# JLC.net
KiCad netlist of a schematic drawn in EasyEDA Pro
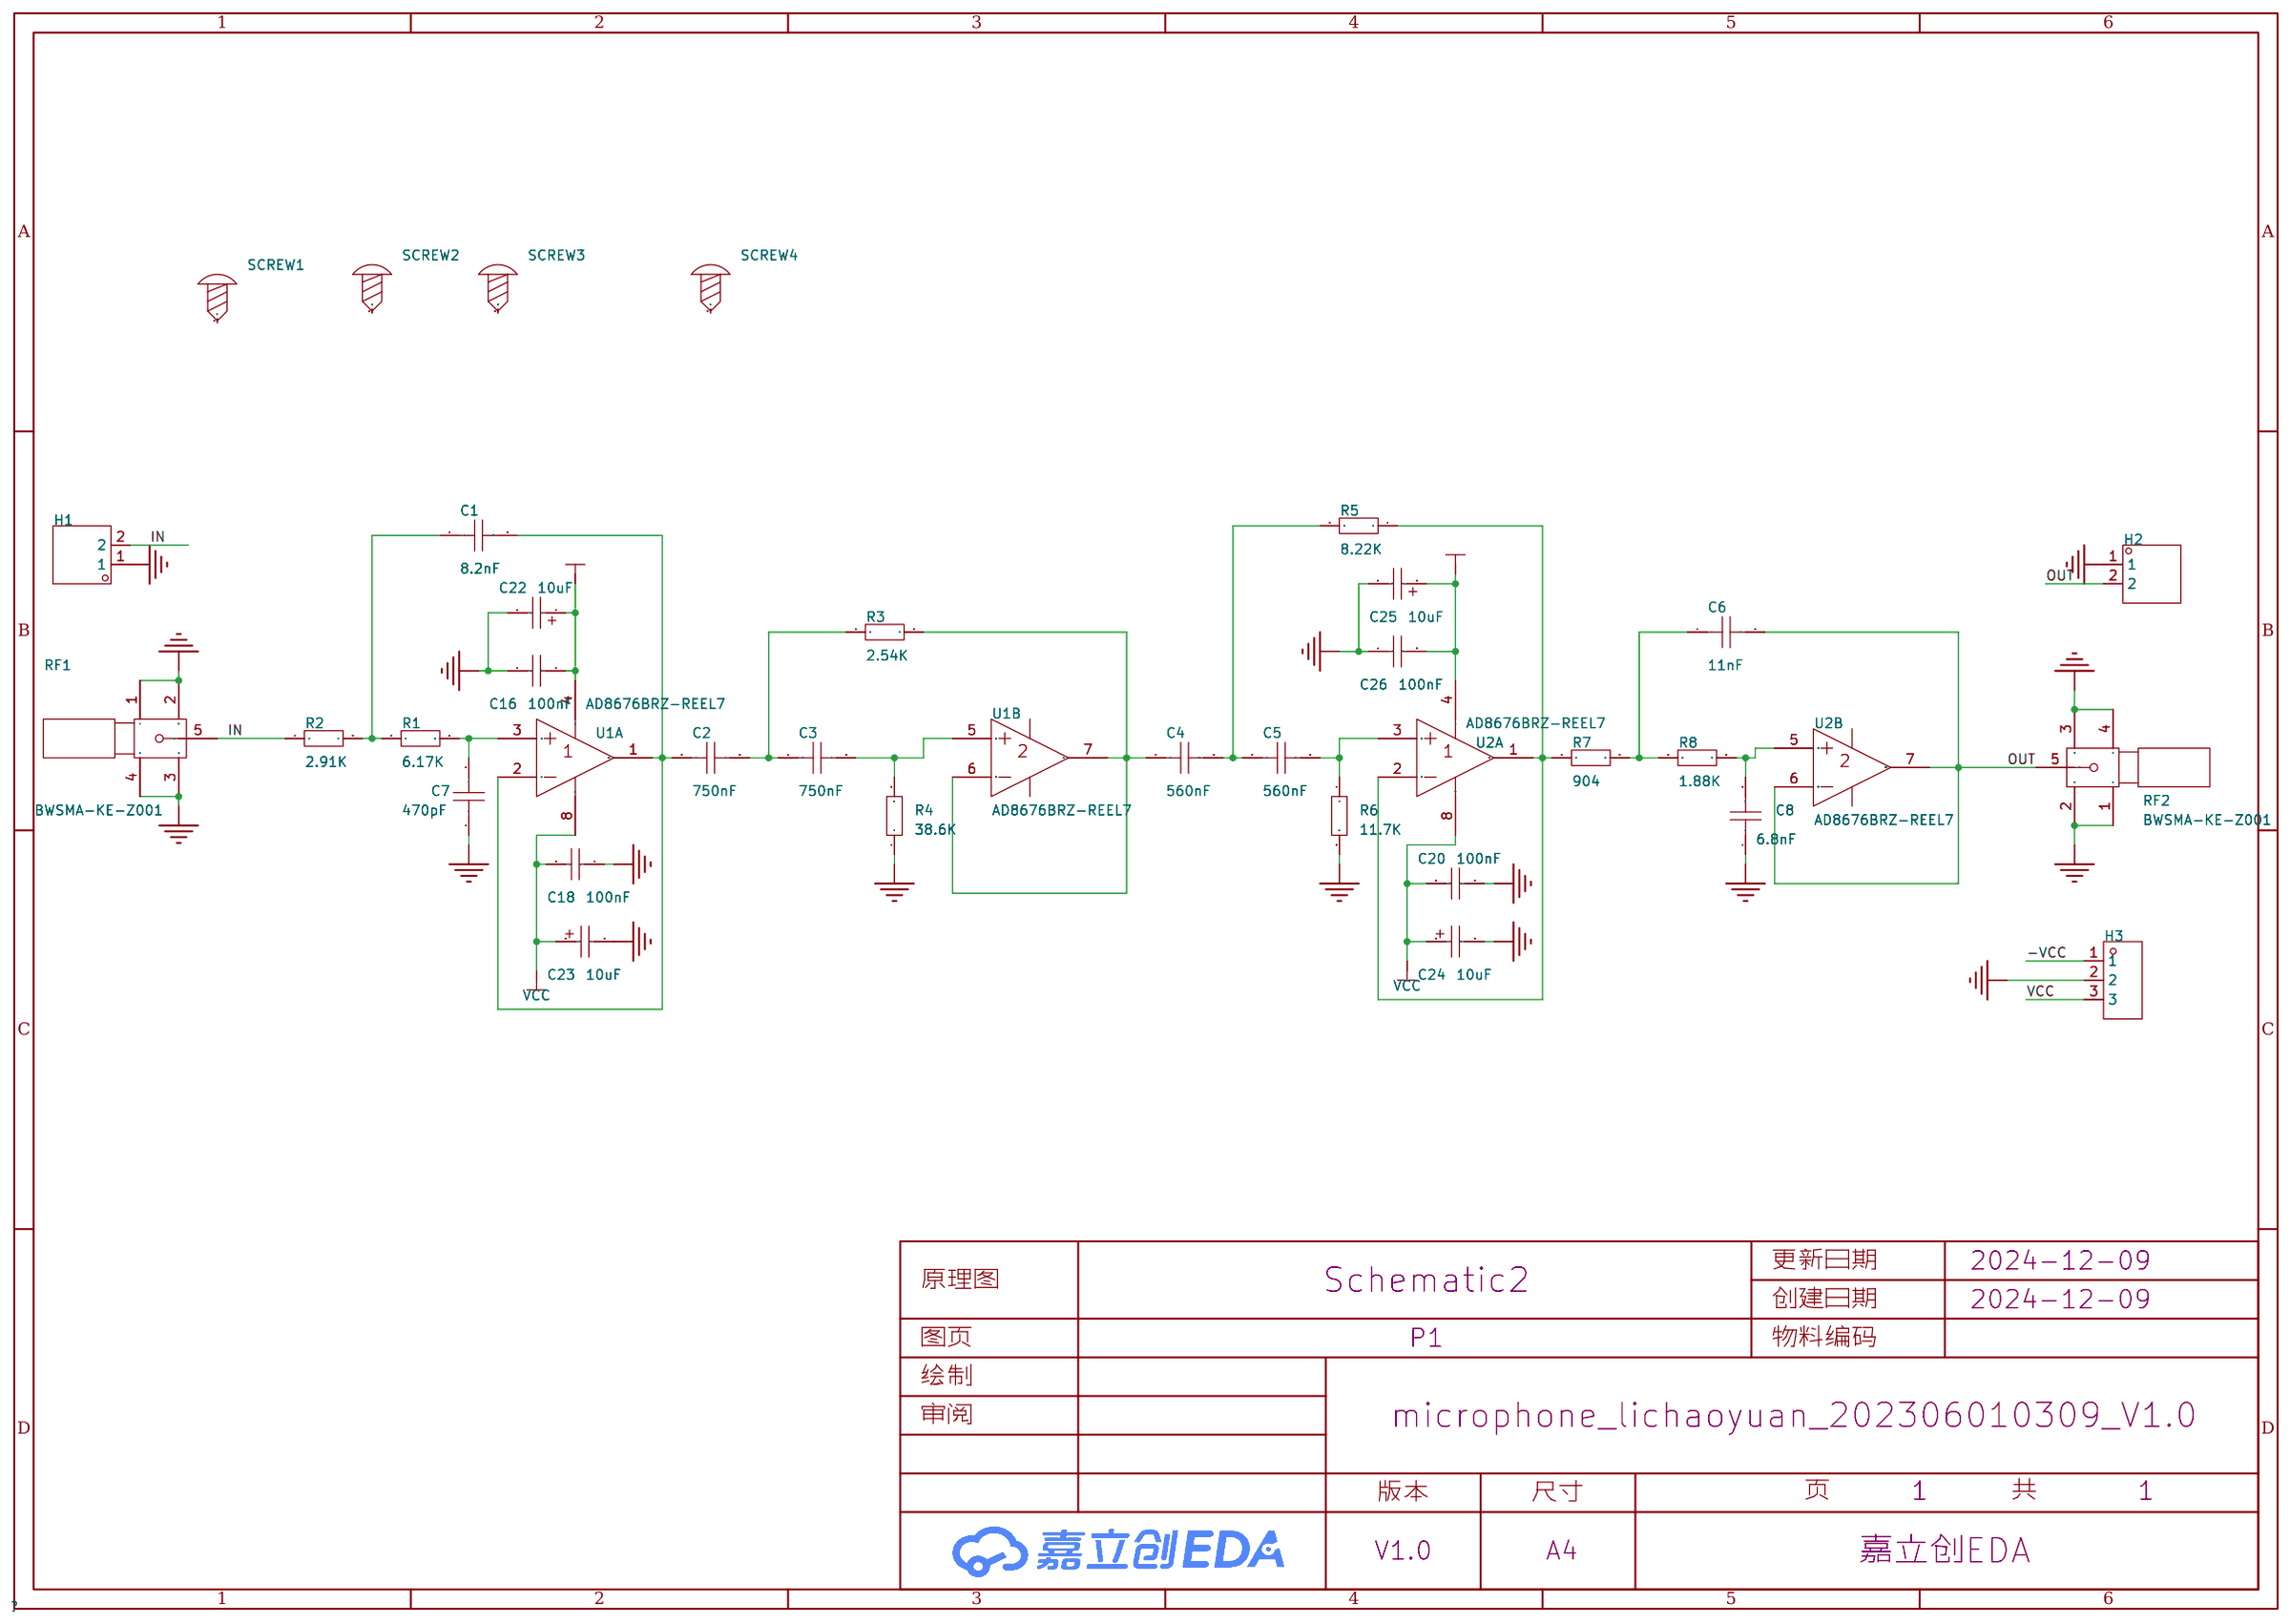
[diagram p0: schematic sheet]

(export (version "E")
  (design (tool "Eeschema 10.0.6"))
  (components
    (comp (ref "C1")
      (value "8.2nF")
      (footprint "easyedapro:C0603")
      (libsource (lib "easyedapro") (part "CapAcitance"))
    )
    (comp (ref "C2")
      (value "750nF")
      (footprint "easyedapro:C0603")
      (libsource (lib "easyedapro") (part "CapAcitance"))
    )
    (comp (ref "C3")
      (value "750nF")
      (footprint "easyedapro:C0603")
      (libsource (lib "easyedapro") (part "CapAcitance"))
    )
    (comp (ref "C4")
      (value "560nF")
      (footprint "easyedapro:C0603")
      (libsource (lib "easyedapro") (part "CapAcitance"))
    )
    (comp (ref "C5")
      (value "560nF")
      (footprint "easyedapro:C0603")
      (libsource (lib "easyedapro") (part "CapAcitance"))
    )
    (comp (ref "C6")
      (value "11nF")
      (footprint "easyedapro:C0603")
      (libsource (lib "easyedapro") (part "CapAcitance"))
    )
    (comp (ref "C7")
      (value "470pF")
      (footprint "easyedapro:C0603")
      (libsource (lib "easyedapro") (part "CapAcitance"))
    )
    (comp (ref "C8")
      (value "6.8nF")
      (footprint "easyedapro:C0603")
      (libsource (lib "easyedapro") (part "CapAcitance"))
    )
    (comp (ref "C16")
      (value "100nF")
      (footprint "easyedapro:C0805")
      (description "容值:100nF;精度:±5%;额定电压:50V;材质(温度系数):X7R;")
      (fields (field (name "Manufacturer Part") "0805B104J500NT") (field (name "Manufacturer") "FH(风华)"))
      (libsource (lib "easyedapro") (part "0805B104J500NT"))
    )
    (comp (ref "C18")
      (value "100nF")
      (footprint "easyedapro:C0805")
      (description "容值:100nF;精度:±5%;额定电压:50V;材质(温度系数):X7R;")
      (fields (field (name "Manufacturer Part") "0805B104J500NT") (field (name "Manufacturer") "FH(风华)"))
      (libsource (lib "easyedapro") (part "0805B104J500NT"))
    )
    (comp (ref "C20")
      (value "100nF")
      (footprint "easyedapro:C0805")
      (description "容值:100nF;精度:±5%;额定电压:50V;材质(温度系数):X7R;")
      (fields (field (name "Manufacturer Part") "0805B104J500NT") (field (name "Manufacturer") "FH(风华)"))
      (libsource (lib "easyedapro") (part "0805B104J500NT"))
    )
    (comp (ref "C22")
      (value "10uF")
      (footprint "easyedapro:C_Ele_SMD_5x5.4mm")
      (libsource (lib "easyedapro") (part "CAP"))
    )
    (comp (ref "C23")
      (value "10uF")
      (footprint "easyedapro:C_Ele_SMD_5x5.4mm")
      (libsource (lib "easyedapro") (part "CAP"))
    )
    (comp (ref "C24")
      (value "10uF")
      (footprint "easyedapro:C_Ele_SMD_5x5.4mm")
      (libsource (lib "easyedapro") (part "CAP"))
    )
    (comp (ref "C25")
      (value "10uF")
      (footprint "easyedapro:C_Ele_SMD_5x5.4mm")
      (libsource (lib "easyedapro") (part "CAP"))
    )
    (comp (ref "C26")
      (value "100nF")
      (footprint "easyedapro:C0805")
      (description "容值:100nF;精度:±5%;额定电压:50V;材质(温度系数):X7R;")
      (fields (field (name "Manufacturer Part") "0805B104J500NT") (field (name "Manufacturer") "FH(风华)"))
      (libsource (lib "easyedapro") (part "0805B104J500NT"))
    )
    (comp (ref "H1")
      (value "~")
      (footprint "easyedapro:HDR-TH_2P-P2.54-V-M-1")
      (libsource (lib "easyedapro") (part "210S-1*2P L=11.6MMGold-plated black"))
    )
    (comp (ref "H2")
      (value "~")
      (footprint "easyedapro:HDR-TH_2P-P2.54-V-M-1")
      (libsource (lib "easyedapro") (part "210S-1*2P L=11.6MMGold-plated black"))
    )
    (comp (ref "H3")
      (value "~")
      (footprint "easyedapro:HDR-TH_3P-P2.54-V-F")
      (libsource (lib "easyedapro") (part "PM254V-11-03-H85"))
    )
    (comp (ref "R1")
      (value "6.17K")
      (footprint "easyedapro:R0603")
      (libsource (lib "easyedapro") (part "电阻"))
    )
    (comp (ref "R2")
      (value "2.91K")
      (footprint "easyedapro:R0603")
      (libsource (lib "easyedapro") (part "电阻"))
    )
    (comp (ref "R3")
      (value "2.54K")
      (footprint "easyedapro:R0603")
      (libsource (lib "easyedapro") (part "电阻"))
    )
    (comp (ref "R4")
      (value "38.6K")
      (footprint "easyedapro:R0603")
      (libsource (lib "easyedapro") (part "电阻"))
    )
    (comp (ref "R5")
      (value "8.22K")
      (footprint "easyedapro:R0603")
      (libsource (lib "easyedapro") (part "电阻"))
    )
    (comp (ref "R6")
      (value "11.7K")
      (footprint "easyedapro:R0603")
      (libsource (lib "easyedapro") (part "电阻"))
    )
    (comp (ref "R7") (value "904") (footprint "easyedapro:R0603") (libsource (lib "easyedapro") (part "电阻")))
    (comp (ref "R8")
      (value "1.88K")
      (footprint "easyedapro:R0603")
      (libsource (lib "easyedapro") (part "电阻"))
    )
    (comp (ref "RF1")
      (value "BWSMA-KE-Z001")
      (footprint "easyedapro:SMA-TH_BWSMA-KE-Z001")
      (fields (field (name "Manufacturer") "BAT WIRELESS(蝙蝠无线)"))
      (libsource (lib "easyedapro") (part "BWSMA-KE-Z001"))
    )
    (comp (ref "RF2")
      (value "BWSMA-KE-Z001")
      (footprint "easyedapro:SMA-TH_BWSMA-KE-Z001")
      (fields (field (name "Manufacturer") "BAT WIRELESS(蝙蝠无线)"))
      (libsource (lib "easyedapro") (part "BWSMA-KE-Z001"))
    )
    (comp (ref "SCREW1")
      (value "~")
      (footprint "easyedapro:M2螺丝")
      (libsource (lib "easyedapro") (part "螺丝孔"))
    )
    (comp (ref "SCREW2")
      (value "~")
      (footprint "easyedapro:M2螺丝")
      (libsource (lib "easyedapro") (part "螺丝孔"))
    )
    (comp (ref "SCREW3")
      (value "~")
      (footprint "easyedapro:M2螺丝")
      (libsource (lib "easyedapro") (part "螺丝孔"))
    )
    (comp (ref "SCREW4")
      (value "~")
      (footprint "easyedapro:M2螺丝")
      (libsource (lib "easyedapro") (part "螺丝孔"))
    )
    (comp (ref "U1")
      (value "AD8676BRZ-REEL7")
      (footprint "easyedapro:SOIC-8_L4.9-W3.9-P1.27-LS6.0-BL")
      (description "超高精度、36 V、2.8 nV/√Hz双路RRO运算放大器")
      (fields (field (name "Manufacturer") "ADI(亚德诺)"))
      (libsource (lib "easyedapro") (part "AD8676BRZ-REEL7"))
    )
    (comp (ref "U2")
      (value "AD8676BRZ-REEL7")
      (footprint "easyedapro:SOIC-8_L4.9-W3.9-P1.27-LS6.0-BL")
      (description "超高精度、36 V、2.8 nV/√Hz双路RRO运算放大器")
      (fields (field (name "Manufacturer") "ADI(亚德诺)"))
      (libsource (lib "easyedapro") (part "AD8676BRZ-REEL7"))
    )
  )
  (nets
    (net (code "1") (name "-VCC") (class "Default")
      (node (ref "C16") (pin "2") (pinfunction "2_2") (pintype "input"))
      (node (ref "C22") (pin "1") (pinfunction "1_1") (pintype "input"))
      (node (ref "C25") (pin "1") (pinfunction "1_1") (pintype "input"))
      (node (ref "C26") (pin "2") (pinfunction "2_2") (pintype "input"))
      (node (ref "H3") (pin "1") (pinfunction "1_1") (pintype "unspecified"))
      (node (ref "U1") (pin "4") (pinfunction "V-_4") (pintype "unspecified"))
      (node (ref "U2") (pin "4") (pinfunction "V-_4") (pintype "unspecified"))
    )
    (net (code "2") (name "/IN") (class "Default")
      (node (ref "H1") (pin "2") (pinfunction "2_2") (pintype "unspecified"))
      (node (ref "R2") (pin "1") (pinfunction "1_1") (pintype "input"))
      (node (ref "RF1") (pin "5") (pinfunction "5_5") (pintype "unspecified"))
    )
    (net (code "3") (name "/OUT") (class "Default")
      (node (ref "C6") (pin "2") (pinfunction "2_2") (pintype "input"))
      (node (ref "H2") (pin "2") (pinfunction "2_2") (pintype "unspecified"))
      (node (ref "RF2") (pin "5") (pinfunction "5_5") (pintype "unspecified"))
      (node (ref "U2") (pin "6") (pinfunction "INB-_6") (pintype "unspecified"))
      (node (ref "U2") (pin "7") (pinfunction "OUTB_7") (pintype "output"))
    )
    (net (code "4") (name "GND") (class "Default")
      (node (ref "C16") (pin "1") (pinfunction "1_1") (pintype "input"))
      (node (ref "C18") (pin "1") (pinfunction "1_1") (pintype "input"))
      (node (ref "C20") (pin "1") (pinfunction "1_1") (pintype "input"))
      (node (ref "C22") (pin "2") (pinfunction "2_2") (pintype "input"))
      (node (ref "C23") (pin "2") (pinfunction "2_2") (pintype "input"))
      (node (ref "C24") (pin "2") (pinfunction "2_2") (pintype "input"))
      (node (ref "C25") (pin "2") (pinfunction "2_2") (pintype "input"))
      (node (ref "C26") (pin "1") (pinfunction "1_1") (pintype "input"))
      (node (ref "C7") (pin "1") (pinfunction "1_1") (pintype "input"))
      (node (ref "C8") (pin "1") (pinfunction "1_1") (pintype "input"))
      (node (ref "H1") (pin "1") (pinfunction "1_1") (pintype "unspecified"))
      (node (ref "H2") (pin "1") (pinfunction "1_1") (pintype "unspecified"))
      (node (ref "H3") (pin "2") (pinfunction "2_2") (pintype "unspecified"))
      (node (ref "R4") (pin "1") (pinfunction "1_1") (pintype "input"))
      (node (ref "R6") (pin "2") (pinfunction "2_2") (pintype "input"))
      (node (ref "RF1") (pin "1") (pinfunction "1_1") (pintype "unspecified"))
      (node (ref "RF1") (pin "2") (pinfunction "2_2") (pintype "unspecified"))
      (node (ref "RF1") (pin "3") (pinfunction "3_3") (pintype "unspecified"))
      (node (ref "RF1") (pin "4") (pinfunction "4_4") (pintype "unspecified"))
      (node (ref "RF2") (pin "1") (pinfunction "1_1") (pintype "unspecified"))
      (node (ref "RF2") (pin "2") (pinfunction "2_2") (pintype "unspecified"))
      (node (ref "RF2") (pin "3") (pinfunction "3_3") (pintype "unspecified"))
      (node (ref "RF2") (pin "4") (pinfunction "4_4") (pintype "unspecified"))
    )
    (net (code "5") (name "Net-(C1-Pad1)") (class "Default")
      (node (ref "C1") (pin "1") (pinfunction "1_1") (pintype "input"))
      (node (ref "R1") (pin "1") (pinfunction "1_1") (pintype "input"))
      (node (ref "R2") (pin "2") (pinfunction "2_2") (pintype "input"))
    )
    (net (code "6") (name "Net-(C2-Pad2)") (class "Default")
      (node (ref "C2") (pin "2") (pinfunction "2_2") (pintype "input"))
      (node (ref "C3") (pin "1") (pinfunction "1_1") (pintype "input"))
      (node (ref "R3") (pin "1") (pinfunction "1_1") (pintype "input"))
    )
    (net (code "7") (name "Net-(C4-Pad2)") (class "Default")
      (node (ref "C4") (pin "2") (pinfunction "2_2") (pintype "input"))
      (node (ref "C5") (pin "1") (pinfunction "1_1") (pintype "input"))
      (node (ref "R5") (pin "2") (pinfunction "2_2") (pintype "input"))
    )
    (net (code "8") (name "Net-(C6-Pad1)") (class "Default")
      (node (ref "C6") (pin "1") (pinfunction "1_1") (pintype "input"))
      (node (ref "R7") (pin "2") (pinfunction "2_2") (pintype "input"))
      (node (ref "R8") (pin "1") (pinfunction "1_1") (pintype "input"))
    )
    (net (code "9") (name "Net-(U1A-INA+)") (class "Default")
      (node (ref "C7") (pin "2") (pinfunction "2_2") (pintype "input"))
      (node (ref "R1") (pin "2") (pinfunction "2_2") (pintype "input"))
      (node (ref "U1") (pin "3") (pinfunction "INA+_3") (pintype "unspecified"))
    )
    (net (code "10") (name "Net-(U1A-INA-)") (class "Default")
      (node (ref "C1") (pin "2") (pinfunction "2_2") (pintype "input"))
      (node (ref "C2") (pin "1") (pinfunction "1_1") (pintype "input"))
      (node (ref "U1") (pin "1") (pinfunction "OUTA_1") (pintype "output"))
      (node (ref "U1") (pin "2") (pinfunction "INA-_2") (pintype "unspecified"))
    )
    (net (code "11") (name "Net-(U1B-INB+)") (class "Default")
      (node (ref "C3") (pin "2") (pinfunction "2_2") (pintype "input"))
      (node (ref "R4") (pin "2") (pinfunction "2_2") (pintype "input"))
      (node (ref "U1") (pin "5") (pinfunction "INB+_5") (pintype "unspecified"))
    )
    (net (code "12") (name "Net-(U1B-INB-)") (class "Default")
      (node (ref "C4") (pin "1") (pinfunction "1_1") (pintype "input"))
      (node (ref "R3") (pin "2") (pinfunction "2_2") (pintype "input"))
      (node (ref "U1") (pin "6") (pinfunction "INB-_6") (pintype "unspecified"))
      (node (ref "U1") (pin "7") (pinfunction "OUTB_7") (pintype "output"))
    )
    (net (code "13") (name "Net-(U2A-INA+)") (class "Default")
      (node (ref "C5") (pin "2") (pinfunction "2_2") (pintype "input"))
      (node (ref "R6") (pin "1") (pinfunction "1_1") (pintype "input"))
      (node (ref "U2") (pin "3") (pinfunction "INA+_3") (pintype "unspecified"))
    )
    (net (code "14") (name "Net-(U2A-INA-)") (class "Default")
      (node (ref "R5") (pin "1") (pinfunction "1_1") (pintype "input"))
      (node (ref "R7") (pin "1") (pinfunction "1_1") (pintype "input"))
      (node (ref "U2") (pin "1") (pinfunction "OUTA_1") (pintype "output"))
      (node (ref "U2") (pin "2") (pinfunction "INA-_2") (pintype "unspecified"))
    )
    (net (code "15") (name "Net-(U2B-INB+)") (class "Default")
      (node (ref "C8") (pin "2") (pinfunction "2_2") (pintype "input"))
      (node (ref "R8") (pin "2") (pinfunction "2_2") (pintype "input"))
      (node (ref "U2") (pin "5") (pinfunction "INB+_5") (pintype "unspecified"))
    )
    (net (code "16") (name "VCC") (class "Default")
      (node (ref "C18") (pin "2") (pinfunction "2_2") (pintype "input"))
      (node (ref "C20") (pin "2") (pinfunction "2_2") (pintype "input"))
      (node (ref "C23") (pin "1") (pinfunction "1_1") (pintype "input"))
      (node (ref "C24") (pin "1") (pinfunction "1_1") (pintype "input"))
      (node (ref "H3") (pin "3") (pinfunction "3_3") (pintype "unspecified"))
      (node (ref "U1") (pin "8") (pinfunction "V+_8") (pintype "unspecified"))
      (node (ref "U2") (pin "8") (pinfunction "V+_8") (pintype "unspecified"))
    )
    (net (code "17") (name "unconnected-(SCREW1-Pad1)") (class "Default")
      (node (ref "SCREW1") (pin "1") (pinfunction "1_1") (pintype "input"))
    )
    (net (code "18") (name "unconnected-(SCREW2-Pad1)") (class "Default")
      (node (ref "SCREW2") (pin "1") (pinfunction "1_1") (pintype "input"))
    )
    (net (code "19") (name "unconnected-(SCREW3-Pad1)") (class "Default")
      (node (ref "SCREW3") (pin "1") (pinfunction "1_1") (pintype "input"))
    )
    (net (code "20") (name "unconnected-(SCREW4-Pad1)") (class "Default")
      (node (ref "SCREW4") (pin "1") (pinfunction "1_1") (pintype "input"))
    )
  )
)
